# RS232.net
KiCad netlist of a schematic drawn in Altium Designer
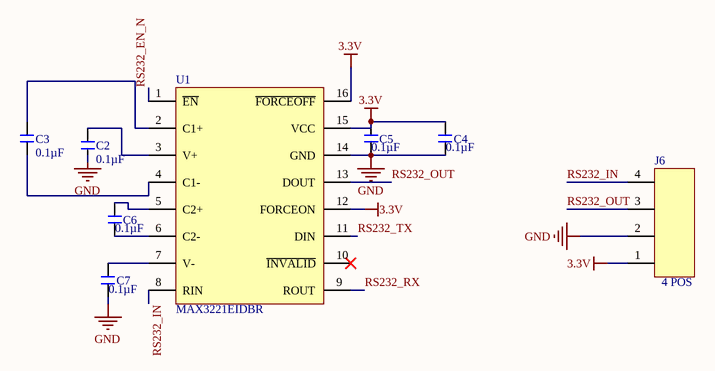
[diagram p0: RS232.SchDoc]

(export (version "E")
  (design (tool "Eeschema 10.0.6"))
  (components
    (comp (ref "C2")
      (value "0.1µF")
      (footprint "402 capacitor - duplicate")
      (description "CAP SMD 402")
      (fields (field (name "MPN") "CL05A104KA5NNNC") (field (name "Comment") "0402 capacitor"))
      (libsource (lib "Schlib1") (part "CAP SMD 402"))
    )
    (comp (ref "C3")
      (value "0.1µF")
      (footprint "402 capacitor - duplicate")
      (description "CAP SMD 402")
      (fields (field (name "MPN") "CL05A104KA5NNNC") (field (name "Comment") "0402 capacitor"))
      (libsource (lib "Schlib1") (part "CAP SMD 402"))
    )
    (comp (ref "C4")
      (value "0.1µF")
      (footprint "402 capacitor - duplicate")
      (description "CAP SMD 402")
      (fields (field (name "MPN") "CL05A104KA5NNNC") (field (name "Comment") "0402 capacitor"))
      (libsource (lib "Schlib1") (part "CAP SMD 402"))
    )
    (comp (ref "C5")
      (value "0.1µF")
      (footprint "402 capacitor - duplicate")
      (description "CAP SMD 402")
      (fields (field (name "MPN") "CL05A104KA5NNNC") (field (name "Comment") "0402 capacitor"))
      (libsource (lib "Schlib1") (part "CAP SMD 402"))
    )
    (comp (ref "C6")
      (value "0.1µF")
      (footprint "402 capacitor - duplicate")
      (description "CAP SMD 402")
      (fields (field (name "MPN") "CL05A104KA5NNNC") (field (name "Comment") "0402 capacitor"))
      (libsource (lib "Schlib1") (part "CAP SMD 402"))
    )
    (comp (ref "C7")
      (value "0.1µF")
      (footprint "402 capacitor - duplicate")
      (description "CAP SMD 402")
      (fields (field (name "MPN") "CL05A104KA5NNNC") (field (name "Comment") "0402 capacitor"))
      (libsource (lib "Schlib1") (part "CAP SMD 402"))
    )
    (comp (ref "J6")
      (value "4 POS")
      (footprint "0901362104")
      (description "CONN HEADER R/A 4POS 2.54MM")
      (fields (field (name "MPN") "0901362104"))
      (libsource (lib "Schlib1") (part "0901362104"))
    )
    (comp (ref "U1")
      (value "MAX3221EIDBR")
      (footprint "MAX3221EIDBR")
      (description "IC TRANSCEIVER FULL 1/1 16SSOP (±5V i±15V - 3kΩ 7kΩ)")
      (libsource (lib "Schlib1") (part "MAX3221EIDBR"))
    )
  )
  (nets
    (net (code "1") (name "/RS232_EN_N") (class "Default")
      (node (ref "U1") (pin "1") (pinfunction "~{EN}_1") (pintype "passive"))
    )
    (net (code "2") (name "/RS232_IN") (class "Default")
      (node (ref "J6") (pin "4") (pintype "passive"))
      (node (ref "U1") (pin "8") (pinfunction "RIN_8") (pintype "passive"))
    )
    (net (code "3") (name "/RS232_OUT") (class "Default")
      (node (ref "J6") (pin "3") (pintype "passive"))
      (node (ref "U1") (pin "13") (pinfunction "DOUT_13") (pintype "passive"))
    )
    (net (code "4") (name "/RS232_RX") (class "Default")
      (node (ref "U1") (pin "9") (pinfunction "ROUT_9") (pintype "passive"))
    )
    (net (code "5") (name "/RS232_TX") (class "Default")
      (node (ref "U1") (pin "11") (pinfunction "DIN_11") (pintype "passive"))
    )
    (net (code "6") (name "3.3V") (class "Default")
      (node (ref "C4") (pin "2") (pintype "passive"))
      (node (ref "C5") (pin "2") (pintype "passive"))
      (node (ref "J6") (pin "1") (pintype "passive"))
      (node (ref "U1") (pin "12") (pinfunction "FORCEON_12") (pintype "passive"))
      (node (ref "U1") (pin "15") (pinfunction "VCC_15") (pintype "passive"))
      (node (ref "U1") (pin "16") (pinfunction "~{FORCEOFF}_16") (pintype "passive"))
    )
    (net (code "7") (name "GND") (class "Default")
      (node (ref "C2") (pin "1") (pintype "passive"))
      (node (ref "C4") (pin "1") (pintype "passive"))
      (node (ref "C5") (pin "1") (pintype "passive"))
      (node (ref "C7") (pin "1") (pintype "passive"))
      (node (ref "J6") (pin "2") (pintype "passive"))
      (node (ref "U1") (pin "14") (pinfunction "GND_14") (pintype "passive"))
    )
    (net (code "8") (name "Net-(U1-C1+)") (class "Default")
      (node (ref "C3") (pin "2") (pintype "passive"))
      (node (ref "U1") (pin "2") (pinfunction "C1+_2") (pintype "passive"))
    )
    (net (code "9") (name "Net-(U1-C1-)") (class "Default")
      (node (ref "C3") (pin "1") (pintype "passive"))
      (node (ref "U1") (pin "4") (pinfunction "C1-_4") (pintype "passive"))
    )
    (net (code "10") (name "Net-(U1-C2+)") (class "Default")
      (node (ref "C6") (pin "2") (pintype "passive"))
      (node (ref "U1") (pin "5") (pinfunction "C2+_5") (pintype "passive"))
    )
    (net (code "11") (name "Net-(U1-C2-)") (class "Default")
      (node (ref "C6") (pin "1") (pintype "passive"))
      (node (ref "U1") (pin "6") (pinfunction "C2-_6") (pintype "passive"))
    )
    (net (code "12") (name "Net-(U1-V+)") (class "Default")
      (node (ref "C2") (pin "2") (pintype "passive"))
      (node (ref "U1") (pin "3") (pinfunction "V+_3") (pintype "passive"))
    )
    (net (code "13") (name "Net-(U1-V-)") (class "Default")
      (node (ref "C7") (pin "2") (pintype "passive"))
      (node (ref "U1") (pin "7") (pinfunction "V-_7") (pintype "passive"))
    )
    (net (code "14") (name "unconnected-(U1-~{INVALID}-Pad10)") (class "Default")
      (node (ref "U1") (pin "10") (pinfunction "~{INVALID}_10") (pintype "passive+no_connect"))
    )
  )
)
